# MCU.net
KiCad netlist of a schematic drawn in Altium Designer
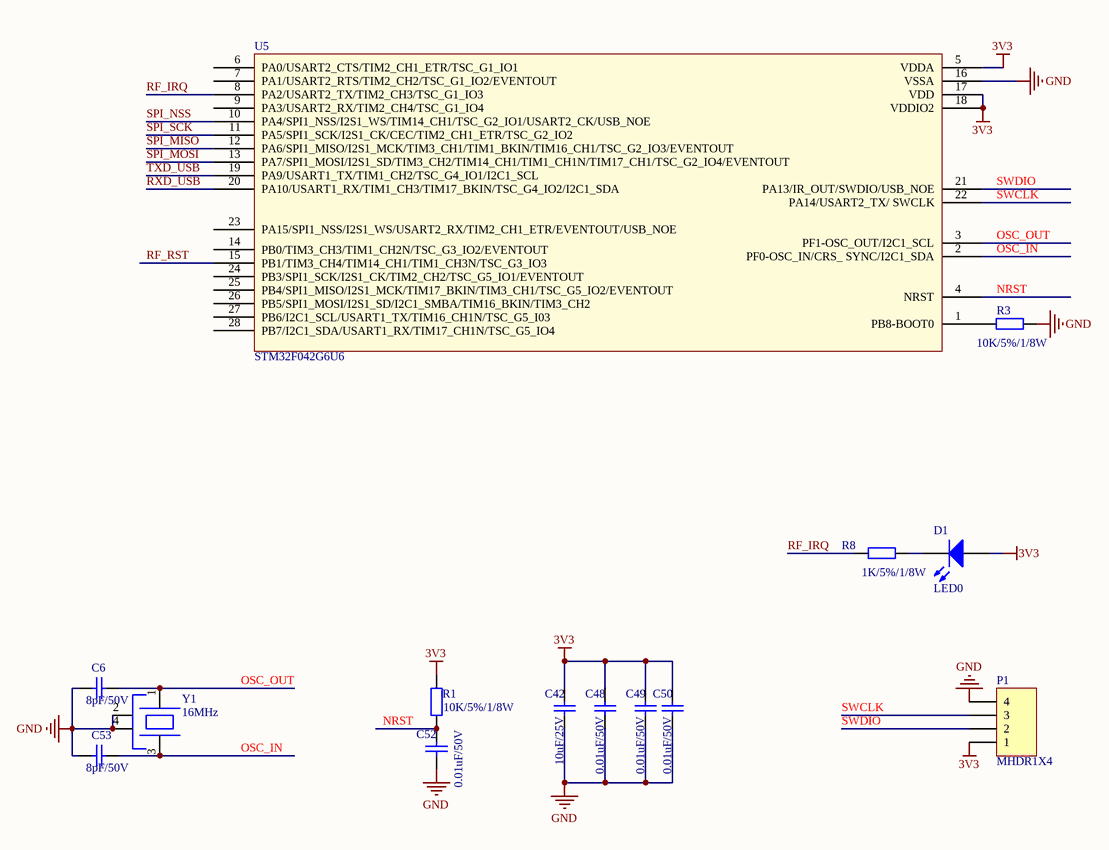
[diagram p0: MCU.SchDoc]

(export (version "E")
  (design (tool "Eeschema 10.0.6"))
  (components
    (comp (ref "C6")
      (value "8pF/50V")
      (footprint "0402C")
      (description "Capacitor")
      (fields (field (name "PUBLISHER") "Altium Limited"))
      (libsource (lib "Miscellaneous Devices") (part "Cap"))
    )
    (comp (ref "C42")
      (value "10uF/25V")
      (footprint "0603C")
      (description "Capacitor")
      (fields (field (name "PUBLISHER") "Altium Limited"))
      (libsource (lib "Miscellaneous Devices") (part "Cap"))
    )
    (comp (ref "C48")
      (value "0.01uF/50V")
      (footprint "0402C")
      (description "Capacitor")
      (fields (field (name "PUBLISHER") "Altium Limited"))
      (libsource (lib "Miscellaneous Devices") (part "Cap"))
    )
    (comp (ref "C49")
      (value "0.01uF/50V")
      (footprint "0402C")
      (description "Capacitor")
      (fields (field (name "PUBLISHER") "Altium Limited"))
      (libsource (lib "Miscellaneous Devices") (part "Cap"))
    )
    (comp (ref "C50")
      (value "0.01uF/50V")
      (footprint "0402C")
      (description "Capacitor")
      (fields (field (name "PUBLISHER") "Altium Limited"))
      (libsource (lib "Miscellaneous Devices") (part "Cap"))
    )
    (comp (ref "C52")
      (value "0.01uF/50V")
      (footprint "0402C")
      (description "Capacitor")
      (fields (field (name "PUBLISHER") "Altium Limited"))
      (libsource (lib "Miscellaneous Devices") (part "Cap"))
    )
    (comp (ref "C53")
      (value "8pF/50V")
      (footprint "0402C")
      (description "Capacitor")
      (fields (field (name "PUBLISHER") "Altium Limited"))
      (libsource (lib "Miscellaneous Devices") (part "Cap"))
    )
    (comp (ref "D1")
      (value "LED0")
      (footprint "0603LED")
      (description "Typical INFRARED GaAs LED")
      (fields (field (name "PUBLISHER") "Altium Limited"))
      (libsource (lib "Miscellaneous Devices") (part "LED0"))
    )
    (comp (ref "P1")
      (value "MHDR1X4")
      (footprint "MHDR1X4")
      (description "Header, 4-Pin")
      (fields (field (name "PUBLISHER") "Altium Limited"))
      (libsource (lib "Miscellaneous Connectors") (part "MHDR1X4"))
    )
    (comp (ref "R1")
      (value "10K/5%/1/8W")
      (footprint "0402R")
      (description "Resistor")
      (fields (field (name "PUBLISHER") "Altium Limited"))
      (libsource (lib "Miscellaneous Devices") (part "Res2"))
    )
    (comp (ref "R3")
      (value "10K/5%/1/8W")
      (footprint "0402R")
      (description "Resistor")
      (fields (field (name "PUBLISHER") "Altium Limited"))
      (libsource (lib "") (part "Res2_1"))
    )
    (comp (ref "R8")
      (value "1K/5%/1/8W")
      (footprint "0402R")
      (description "Resistor")
      (fields (field (name "PUBLISHER") "Altium Limited"))
      (libsource (lib "") (part "Res2_1"))
    )
    (comp (ref "U5")
      (value "STM32F042G6U6")
      (footprint "UFQFPN28")
      (libsource (lib "GPS2") (part "STM32F042G6U6"))
    )
    (comp (ref "Y1")
      (value "16MHz")
      (footprint "OSCILLATOR-3.2X2.5")
      (libsource (lib "Myself_1") (part "XTAL3"))
    )
  )
  (nets
    (net (code "1") (name "/NRST") (class "Default")
      (node (ref "C52") (pin "1") (pinfunction "1_1") (pintype "passive"))
      (node (ref "R1") (pin "1") (pinfunction "1_1") (pintype "passive"))
      (node (ref "U5") (pin "4") (pinfunction "NRST_4") (pintype "passive"))
    )
    (net (code "2") (name "/OSC_IN") (class "Default")
      (node (ref "C53") (pin "2") (pinfunction "2_2") (pintype "passive"))
      (node (ref "U5") (pin "2") (pinfunction "PF0-OSC_IN/CRS__SYNC/I2C1_SDA_2") (pintype "passive"))
      (node (ref "Y1") (pin "3") (pinfunction "3_3") (pintype "passive"))
    )
    (net (code "3") (name "/OSC_OUT") (class "Default")
      (node (ref "C6") (pin "2") (pinfunction "2_2") (pintype "passive"))
      (node (ref "U5") (pin "3") (pinfunction "PF1-OSC_OUT/I2C1_SCL_3") (pintype "passive"))
      (node (ref "Y1") (pin "1") (pinfunction "1_1") (pintype "passive"))
    )
    (net (code "4") (name "/RF_IRQ") (class "Default")
      (node (ref "R8") (pin "2") (pinfunction "2_2") (pintype "passive"))
      (node (ref "U5") (pin "8") (pinfunction "PA2/USART2_TX/TIM2_CH3/TSC_G1_IO3_8") (pintype "passive"))
    )
    (net (code "5") (name "/RF_RST") (class "Default")
      (node (ref "U5") (pin "15") (pinfunction "PB1/TIM3_CH4/TIM14_CH1/TIM1_CH3N/TSC_G3_IO3_15") (pintype "passive"))
    )
    (net (code "6") (name "/RXD_USB") (class "Default")
      (node (ref "U5") (pin "20") (pinfunction "PA10/USART1_RX/TIM1_CH3/TIM17_BKIN/TSC_G4_IO2/I2C1_SDA_20") (pintype "passive"))
    )
    (net (code "7") (name "/SPI_MISO") (class "Default")
      (node (ref "U5") (pin "12") (pinfunction "PA6/SPI1_MISO/I2S1_MCK/TIM3_CH1/TIM1_BKIN/TIM16_CH1/TSC_G2_IO3/EVENTOUT_12") (pintype "passive"))
    )
    (net (code "8") (name "/SPI_MOSI") (class "Default")
      (node (ref "U5") (pin "13") (pinfunction "PA7/SPI1_MOSI/I2S1_SD/TIM3_CH2/TIM14_CH1/TIM1_CH1N/TIM17_CH1/TSC_G2_IO4/EVENTOUT_13") (pintype "passive"))
    )
    (net (code "9") (name "/SPI_NSS") (class "Default")
      (node (ref "U5") (pin "10") (pinfunction "PA4/SPI1_NSS/I2S1_WS/TIM14_CH1/TSC_G2_IO1/USART2_CK/USB_NOE_10") (pintype "passive"))
    )
    (net (code "10") (name "/SPI_SCK") (class "Default")
      (node (ref "U5") (pin "11") (pinfunction "PA5/SPI1_SCK/I2S1_CK/CEC/TIM2_CH1_ETR/TSC_G2_IO2_11") (pintype "passive"))
    )
    (net (code "11") (name "/SWCLK") (class "Default")
      (node (ref "P1") (pin "3") (pinfunction "3_3") (pintype "passive"))
      (node (ref "U5") (pin "22") (pinfunction "PA14/USART2_TX/_SWCLK_22") (pintype "passive"))
    )
    (net (code "12") (name "/SWDIO") (class "Default")
      (node (ref "P1") (pin "2") (pinfunction "2_2") (pintype "passive"))
      (node (ref "U5") (pin "21") (pinfunction "PA13/IR_OUT/SWDIO/USB_NOE_21") (pintype "passive"))
    )
    (net (code "13") (name "/TXD_USB") (class "Default")
      (node (ref "U5") (pin "19") (pinfunction "PA9/USART1_TX/TIM1_CH2/TSC_G4_IO1/I2C1_SCL_19") (pintype "passive"))
    )
    (net (code "14") (name "3V3") (class "Default")
      (node (ref "C42") (pin "1") (pinfunction "1_1") (pintype "passive"))
      (node (ref "C48") (pin "1") (pinfunction "1_1") (pintype "passive"))
      (node (ref "C49") (pin "1") (pinfunction "1_1") (pintype "passive"))
      (node (ref "C50") (pin "1") (pinfunction "1_1") (pintype "passive"))
      (node (ref "D1") (pin "1") (pinfunction "A_1") (pintype "passive"))
      (node (ref "P1") (pin "1") (pinfunction "1_1") (pintype "passive"))
      (node (ref "R1") (pin "2") (pinfunction "2_2") (pintype "passive"))
      (node (ref "U5") (pin "17") (pinfunction "VDD_17") (pintype "passive"))
      (node (ref "U5") (pin "18") (pinfunction "VDDIO2_18") (pintype "passive"))
      (node (ref "U5") (pin "5") (pinfunction "VDDA_5") (pintype "passive"))
    )
    (net (code "15") (name "GND") (class "Default")
      (node (ref "C42") (pin "2") (pinfunction "2_2") (pintype "passive"))
      (node (ref "C48") (pin "2") (pinfunction "2_2") (pintype "passive"))
      (node (ref "C49") (pin "2") (pinfunction "2_2") (pintype "passive"))
      (node (ref "C50") (pin "2") (pinfunction "2_2") (pintype "passive"))
      (node (ref "C52") (pin "2") (pinfunction "2_2") (pintype "passive"))
      (node (ref "C53") (pin "1") (pinfunction "1_1") (pintype "passive"))
      (node (ref "C6") (pin "1") (pinfunction "1_1") (pintype "passive"))
      (node (ref "P1") (pin "4") (pinfunction "4_4") (pintype "passive"))
      (node (ref "R3") (pin "1") (pinfunction "1_1") (pintype "passive"))
      (node (ref "U5") (pin "16") (pinfunction "VSSA_16") (pintype "passive"))
      (node (ref "Y1") (pin "2") (pinfunction "GND_2") (pintype "passive"))
      (node (ref "Y1") (pin "4") (pinfunction "GND_4") (pintype "passive"))
    )
    (net (code "16") (name "Net-(D1-K)") (class "Default")
      (node (ref "D1") (pin "2") (pinfunction "K_2") (pintype "passive"))
      (node (ref "R8") (pin "1") (pinfunction "1_1") (pintype "passive"))
    )
    (net (code "17") (name "Net-(U5-PB8-BOOT0)") (class "Default")
      (node (ref "R3") (pin "2") (pinfunction "2_2") (pintype "passive"))
      (node (ref "U5") (pin "1") (pinfunction "PB8-BOOT0_1") (pintype "passive"))
    )
    (net (code "18") (name "unconnected-(U5-PA0{slash}USART2_CTS{slash}TIM2_CH1_ETR{slash}TSC_G1_IO1-Pad6)") (class "Default")
      (node (ref "U5") (pin "6") (pinfunction "PA0/USART2_CTS/TIM2_CH1_ETR/TSC_G1_IO1_6") (pintype "passive"))
    )
    (net (code "19") (name "unconnected-(U5-PA1{slash}USART2_RTS{slash}TIM2_CH2{slash}TSC_G1_IO2{slash}EVENTOUT-Pad7)") (class "Default")
      (node (ref "U5") (pin "7") (pinfunction "PA1/USART2_RTS/TIM2_CH2/TSC_G1_IO2/EVENTOUT_7") (pintype "passive"))
    )
    (net (code "20") (name "unconnected-(U5-PA3{slash}USART2_RX{slash}TIM2_CH4{slash}TSC_G1_IO4-Pad9)") (class "Default")
      (node (ref "U5") (pin "9") (pinfunction "PA3/USART2_RX/TIM2_CH4/TSC_G1_IO4_9") (pintype "passive"))
    )
    (net (code "21") (name "unconnected-(U5-PA15{slash}SPI1_NSS{slash}I2S1_WS{slash}USART2_RX{slash}TIM2_CH1_ETR{slash}EVENTOUT{slash}USB_NOE-Pad23)") (class "Default")
      (node (ref "U5") (pin "23") (pinfunction "PA15/SPI1_NSS/I2S1_WS/USART2_RX/TIM2_CH1_ETR/EVENTOUT/USB_NOE_23") (pintype "passive"))
    )
    (net (code "22") (name "unconnected-(U5-PB0{slash}TIM3_CH3{slash}TIM1_CH2N{slash}TSC_G3_IO2{slash}EVENTOUT-Pad14)") (class "Default")
      (node (ref "U5") (pin "14") (pinfunction "PB0/TIM3_CH3/TIM1_CH2N/TSC_G3_IO2/EVENTOUT_14") (pintype "passive"))
    )
    (net (code "23") (name "unconnected-(U5-PB3{slash}SPI1_SCK{slash}I2S1_CK{slash}TIM2_CH2{slash}TSC_G5_IO1{slash}EVENTOUT-Pad24)") (class "Default")
      (node (ref "U5") (pin "24") (pinfunction "PB3/SPI1_SCK/I2S1_CK/TIM2_CH2/TSC_G5_IO1/EVENTOUT_24") (pintype "passive"))
    )
    (net (code "24") (name "unconnected-(U5-PB4{slash}SPI1_MISO{slash}I2S1_MCK{slash}TIM17_BKIN{slash}TIM3_CH1{slash}TSC_G5_IO2{slash}EVENTOUT-Pad25)") (class "Default")
      (node (ref "U5") (pin "25") (pinfunction "PB4/SPI1_MISO/I2S1_MCK/TIM17_BKIN/TIM3_CH1/TSC_G5_IO2/EVENTOUT_25") (pintype "passive"))
    )
    (net (code "25") (name "unconnected-(U5-PB5{slash}SPI1_MOSI{slash}I2S1_SD{slash}I2C1_SMBA{slash}TIM16_BKIN{slash}TIM3_CH2-Pad26)") (class "Default")
      (node (ref "U5") (pin "26") (pinfunction "PB5/SPI1_MOSI/I2S1_SD/I2C1_SMBA/TIM16_BKIN/TIM3_CH2_26") (pintype "passive"))
    )
    (net (code "26") (name "unconnected-(U5-PB6{slash}I2C1_SCL{slash}USART1_TX{slash}TIM16_CH1N{slash}TSC_G5_I03-Pad27)") (class "Default")
      (node (ref "U5") (pin "27") (pinfunction "PB6/I2C1_SCL/USART1_TX/TIM16_CH1N/TSC_G5_I03_27") (pintype "passive"))
    )
    (net (code "27") (name "unconnected-(U5-PB7{slash}I2C1_SDA{slash}USART1_RX{slash}TIM17_CH1N{slash}TSC_G5_IO4-Pad28)") (class "Default")
      (node (ref "U5") (pin "28") (pinfunction "PB7/I2C1_SDA/USART1_RX/TIM17_CH1N/TSC_G5_IO4_28") (pintype "passive"))
    )
  )
)
